# PowCarbinBoard_Isolation.net
KiCad netlist of a schematic drawn in Altium Designer
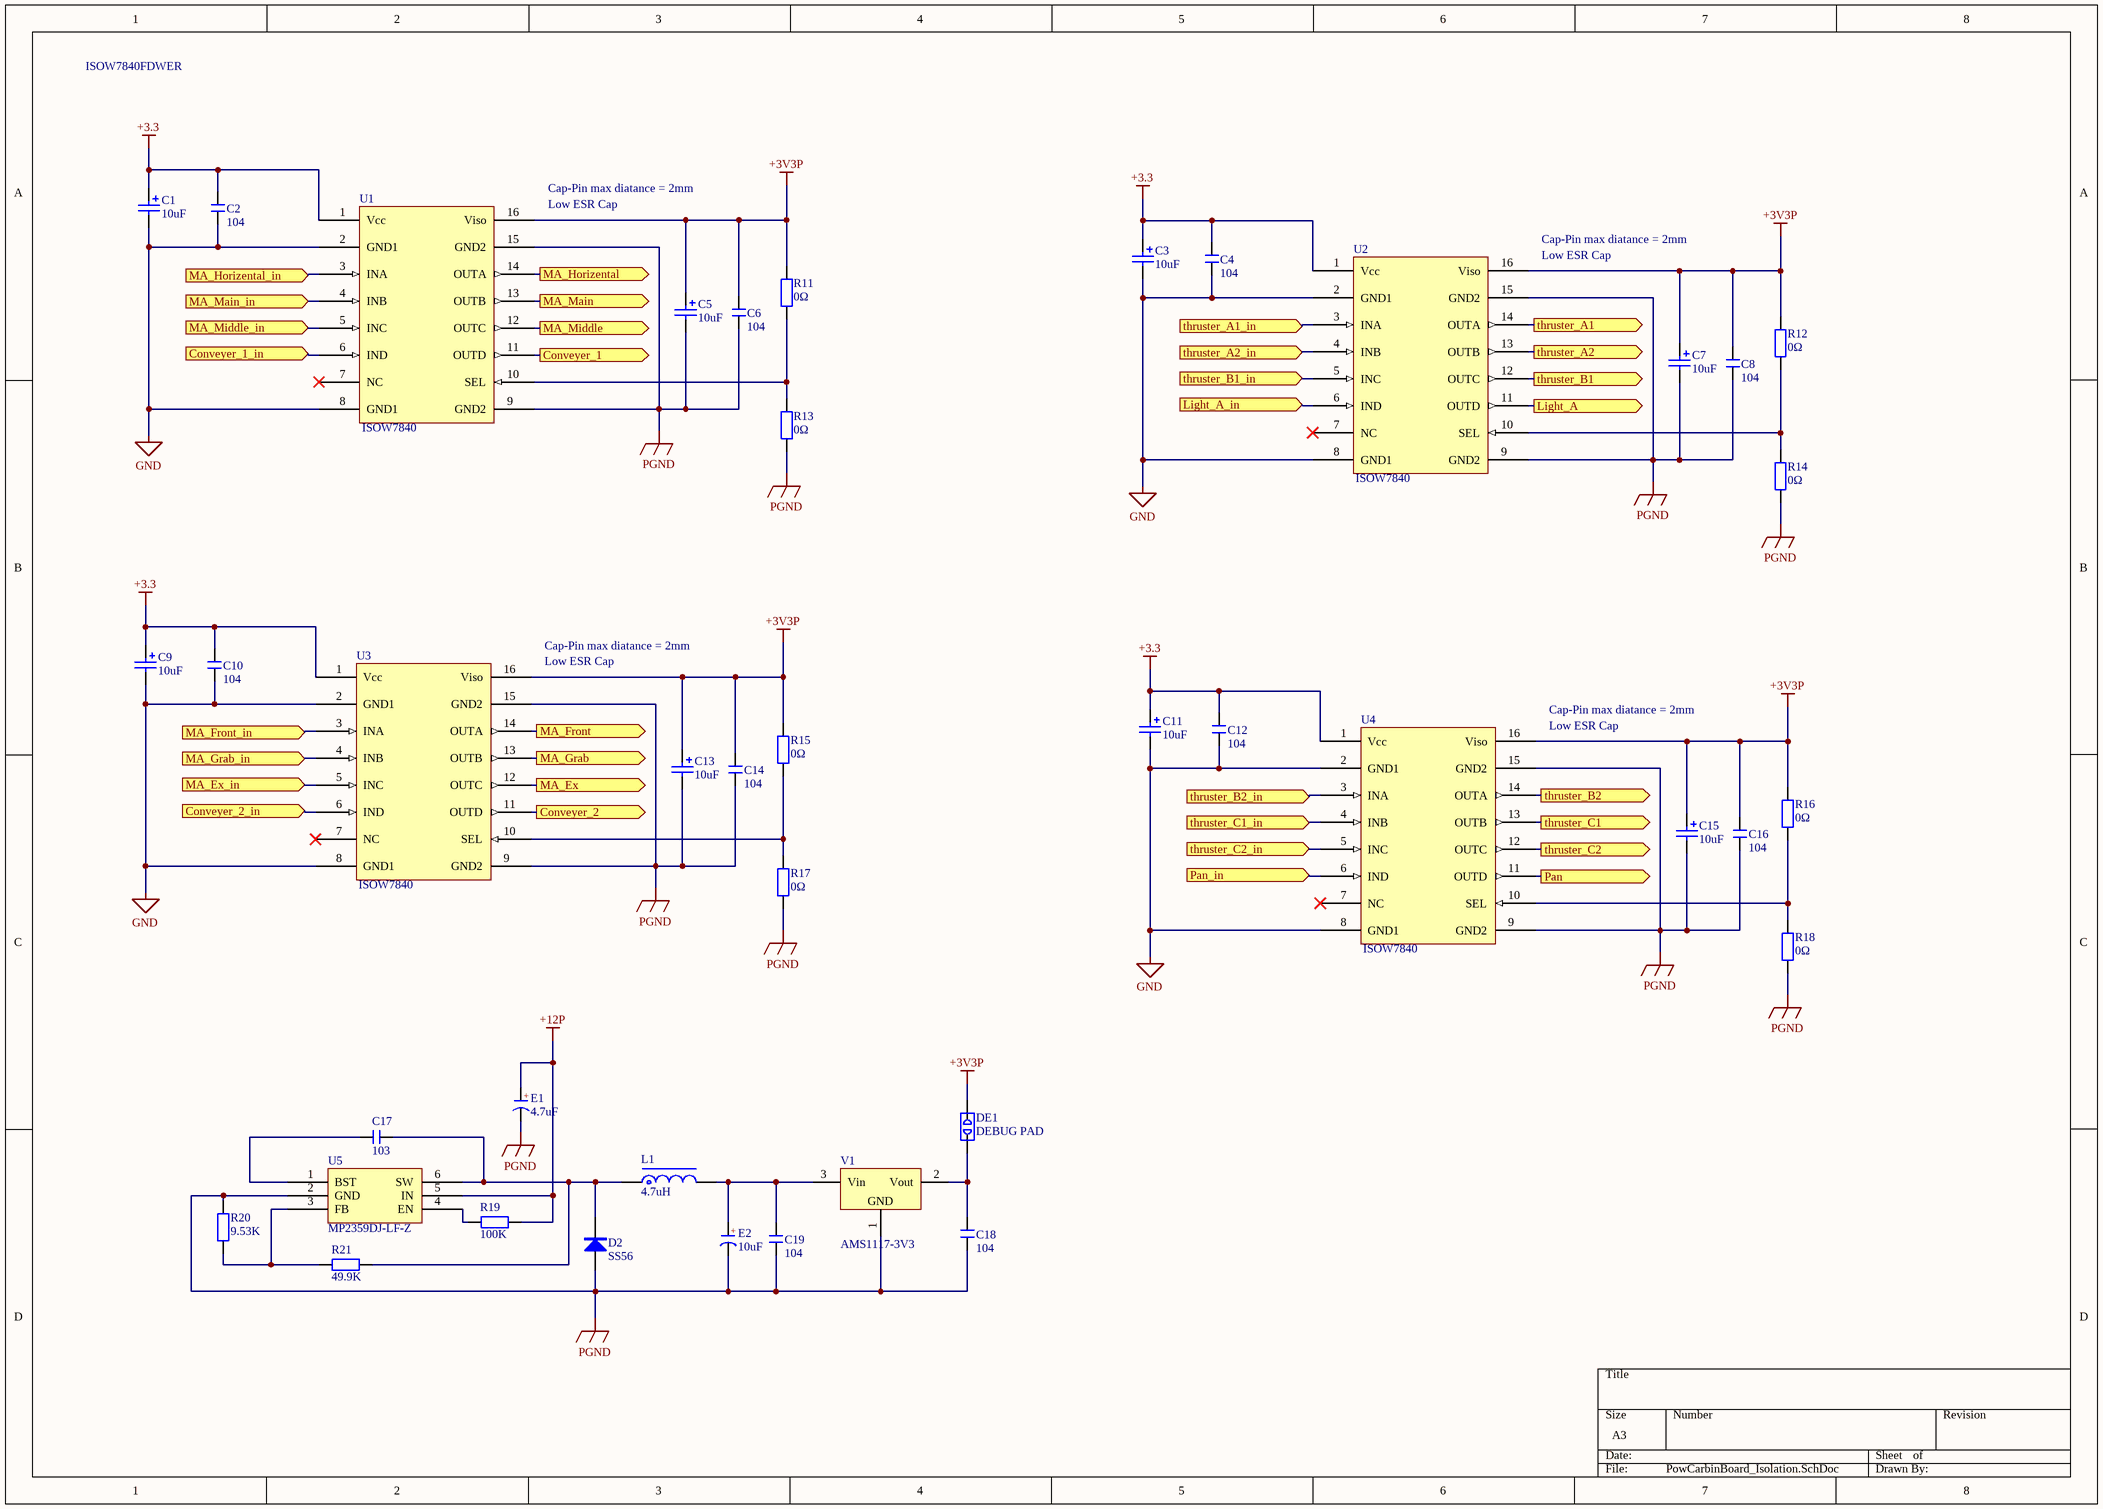
[diagram p0: PowCarbinBoard_Isolation.SchDoc]

(export (version "E")
  (design (tool "Eeschema 10.0.6"))
  (components
    (comp (ref "C1")
      (value "10uF")
      (footprint "CASE-B_3528")
      (description "钽电容")
      (libsource (lib "Miscellaneous Devices LC") (part "3528 100uF (107) 10% 6.3V"))
    )
    (comp (ref "C2")
      (value "104")
      (footprint "C 0603_L")
      (description "无极性贴片电容")
      (fields (field (name "版权归属") "源创客"))
      (libsource (lib "3.1   - 电阻-电容-电感") (part "C"))
    )
    (comp (ref "C3")
      (value "10uF")
      (footprint "CASE-B_3528")
      (description "钽电容")
      (libsource (lib "Miscellaneous Devices LC") (part "3528 100uF (107) 10% 6.3V"))
    )
    (comp (ref "C4")
      (value "104")
      (footprint "C 0603_L")
      (description "无极性贴片电容")
      (fields (field (name "版权归属") "源创客"))
      (libsource (lib "3.1   - 电阻-电容-电感") (part "C"))
    )
    (comp (ref "C5")
      (value "10uF")
      (footprint "CASE-B_3528")
      (description "钽电容")
      (libsource (lib "Miscellaneous Devices LC") (part "3528 100uF (107) 10% 6.3V"))
    )
    (comp (ref "C6")
      (value "104")
      (footprint "C 0603_L")
      (description "无极性贴片电容")
      (fields (field (name "版权归属") "源创客"))
      (libsource (lib "3.1   - 电阻-电容-电感") (part "C"))
    )
    (comp (ref "C7")
      (value "10uF")
      (footprint "CASE-B_3528")
      (description "钽电容")
      (libsource (lib "Miscellaneous Devices LC") (part "3528 100uF (107) 10% 6.3V"))
    )
    (comp (ref "C8")
      (value "104")
      (footprint "C 0603_L")
      (description "无极性贴片电容")
      (fields (field (name "版权归属") "源创客"))
      (libsource (lib "3.1   - 电阻-电容-电感") (part "C"))
    )
    (comp (ref "C9")
      (value "10uF")
      (footprint "CASE-B_3528")
      (description "钽电容")
      (libsource (lib "Miscellaneous Devices LC") (part "3528 100uF (107) 10% 6.3V"))
    )
    (comp (ref "C10")
      (value "104")
      (footprint "C 0603_L")
      (description "无极性贴片电容")
      (fields (field (name "版权归属") "源创客"))
      (libsource (lib "3.1   - 电阻-电容-电感") (part "C"))
    )
    (comp (ref "C11")
      (value "10uF")
      (footprint "CASE-B_3528")
      (description "钽电容")
      (libsource (lib "Miscellaneous Devices LC") (part "3528 100uF (107) 10% 6.3V"))
    )
    (comp (ref "C12")
      (value "104")
      (footprint "C 0603_L")
      (description "无极性贴片电容")
      (fields (field (name "版权归属") "源创客"))
      (libsource (lib "3.1   - 电阻-电容-电感") (part "C"))
    )
    (comp (ref "C13")
      (value "10uF")
      (footprint "CASE-B_3528")
      (description "钽电容")
      (libsource (lib "Miscellaneous Devices LC") (part "3528 100uF (107) 10% 6.3V"))
    )
    (comp (ref "C14")
      (value "104")
      (footprint "C 0603_L")
      (description "无极性贴片电容")
      (fields (field (name "版权归属") "源创客"))
      (libsource (lib "3.1   - 电阻-电容-电感") (part "C"))
    )
    (comp (ref "C15")
      (value "10uF")
      (footprint "CASE-B_3528")
      (description "钽电容")
      (libsource (lib "Miscellaneous Devices LC") (part "3528 100uF (107) 10% 6.3V"))
    )
    (comp (ref "C16")
      (value "104")
      (footprint "C 0603_L")
      (description "无极性贴片电容")
      (fields (field (name "版权归属") "源创客"))
      (libsource (lib "3.1   - 电阻-电容-电感") (part "C"))
    )
    (comp (ref "C17")
      (value "103")
      (footprint "C 0603_L")
      (description "无极性贴片电容")
      (fields (field (name "版权归属") "源创客"))
      (libsource (lib "3.1   - 电阻-电容-电感") (part "C"))
    )
    (comp (ref "C18")
      (value "104")
      (footprint "C 0603_L")
      (description "无极性贴片电容")
      (fields (field (name "版权归属") "源创客"))
      (libsource (lib "3.1   - 电阻-电容-电感") (part "C"))
    )
    (comp (ref "C19")
      (value "104")
      (footprint "C 0603_L")
      (description "无极性贴片电容")
      (fields (field (name "版权归属") "源创客"))
      (libsource (lib "3.1   - 电阻-电容-电感") (part "C"))
    )
    (comp (ref "D2")
      (value "SS56")
      (footprint "SMA")
      (description "肖特基二极管")
      (fields (field (name "版权归属") "源创客"))
      (libsource (lib "8.1   - 二极管-整流桥") (part "SS14"))
    )
    (comp (ref "DE1")
      (value "DEBUG PAD")
      (footprint "DEBUG_A")
      (description "调试断点焊盘")
      (fields (field (name "版权归属") "源创客"))
      (libsource (lib "15.1 - 未分类器件") (part "DEBUG"))
    )
    (comp (ref "E1")
      (value "4.7uF")
      (footprint "CM B(4*5.4)")
      (description "贴片电解电容")
      (fields (field (name "版权归属") "源创客"))
      (libsource (lib "3.1   - 电阻-电容-电感") (part "C-CM"))
    )
    (comp (ref "E2")
      (value "10uF")
      (footprint "CM B(4*5.4)")
      (description "贴片电解电容")
      (fields (field (name "版权归属") "源创客"))
      (libsource (lib "3.1   - 电阻-电容-电感") (part "C-CM"))
    )
    (comp (ref "L1")
      (value "4.7uH")
      (footprint "CDRH74")
      (description "功率屏蔽电感")
      (fields (field (name "版权归属") "源创客"))
      (libsource (lib "3.1   - 电阻-电容-电感") (part "L-CDRH"))
    )
    (comp (ref "R11")
      (value "0Ω")
      (footprint "R 0603_L")
      (description "贴片电阻")
      (fields (field (name "版权归属") "源创客"))
      (libsource (lib "3.1   - 电阻-电容-电感") (part "R"))
    )
    (comp (ref "R12")
      (value "0Ω")
      (footprint "R 0603_L")
      (description "贴片电阻")
      (fields (field (name "版权归属") "源创客"))
      (libsource (lib "3.1   - 电阻-电容-电感") (part "R"))
    )
    (comp (ref "R13")
      (value "0Ω")
      (footprint "R 0603_L")
      (description "贴片电阻")
      (fields (field (name "版权归属") "源创客"))
      (libsource (lib "3.1   - 电阻-电容-电感") (part "R"))
    )
    (comp (ref "R14")
      (value "0Ω")
      (footprint "R 0603_L")
      (description "贴片电阻")
      (fields (field (name "版权归属") "源创客"))
      (libsource (lib "3.1   - 电阻-电容-电感") (part "R"))
    )
    (comp (ref "R15")
      (value "0Ω")
      (footprint "R 0603_L")
      (description "贴片电阻")
      (fields (field (name "版权归属") "源创客"))
      (libsource (lib "3.1   - 电阻-电容-电感") (part "R"))
    )
    (comp (ref "R16")
      (value "0Ω")
      (footprint "R 0603_L")
      (description "贴片电阻")
      (fields (field (name "版权归属") "源创客"))
      (libsource (lib "3.1   - 电阻-电容-电感") (part "R"))
    )
    (comp (ref "R17")
      (value "0Ω")
      (footprint "R 0603_L")
      (description "贴片电阻")
      (fields (field (name "版权归属") "源创客"))
      (libsource (lib "3.1   - 电阻-电容-电感") (part "R"))
    )
    (comp (ref "R18")
      (value "0Ω")
      (footprint "R 0603_L")
      (description "贴片电阻")
      (fields (field (name "版权归属") "源创客"))
      (libsource (lib "3.1   - 电阻-电容-电感") (part "R"))
    )
    (comp (ref "R19")
      (value "100K")
      (footprint "R 0603_L")
      (description "贴片电阻")
      (fields (field (name "版权归属") "源创客"))
      (libsource (lib "3.1   - 电阻-电容-电感") (part "R"))
    )
    (comp (ref "R20")
      (value "9.53K")
      (footprint "R 0603_L")
      (description "贴片电阻")
      (fields (field (name "版权归属") "源创客"))
      (libsource (lib "3.1   - 电阻-电容-电感") (part "R"))
    )
    (comp (ref "R21")
      (value "49.9K")
      (footprint "R 0603_L")
      (description "贴片电阻")
      (fields (field (name "版权归属") "源创客"))
      (libsource (lib "3.1   - 电阻-电容-电感") (part "R"))
    )
    (comp (ref "U1") (value "ISOW7840") (footprint "ISOW7840") (libsource (lib "Schlib1") (part "ISOW7840")))
    (comp (ref "U2") (value "ISOW7840") (footprint "ISOW7840") (libsource (lib "Schlib1") (part "ISOW7840")))
    (comp (ref "U3") (value "ISOW7840") (footprint "ISOW7840") (libsource (lib "Schlib1") (part "ISOW7840")))
    (comp (ref "U4") (value "ISOW7840") (footprint "ISOW7840") (libsource (lib "Schlib1") (part "ISOW7840")))
    (comp (ref "U5")
      (value "MP2359DJ-LF-Z")
      (footprint "SOT-23-6")
      (description "DC-DC芯片")
      (libsource (lib "Miscellaneous Devices LC") (part "MP2359DJ-LF-Z_[C14259]"))
    )
    (comp (ref "V1")
      (value "AMS1117-3V3")
      (footprint "SOT89_N")
      (description "三端稳压芯片")
      (fields (field (name "版权归属") "源创客"))
      (libsource (lib "1.3   - 电源类芯片") (part "AMS1117"))
    )
  )
  (nets
    (net (code "1") (name "+3.3") (class "Default")
      (node (ref "C1") (pin "1") (pinfunction "1_1") (pintype "passive"))
      (node (ref "C10") (pin "2") (pinfunction "2_2") (pintype "passive"))
      (node (ref "C11") (pin "1") (pinfunction "1_1") (pintype "passive"))
      (node (ref "C12") (pin "2") (pinfunction "2_2") (pintype "passive"))
      (node (ref "C2") (pin "2") (pinfunction "2_2") (pintype "passive"))
      (node (ref "C3") (pin "1") (pinfunction "1_1") (pintype "passive"))
      (node (ref "C4") (pin "2") (pinfunction "2_2") (pintype "passive"))
      (node (ref "C9") (pin "1") (pinfunction "1_1") (pintype "passive"))
      (node (ref "U1") (pin "1") (pinfunction "Vcc_1") (pintype "power_in"))
      (node (ref "U2") (pin "1") (pinfunction "Vcc_1") (pintype "power_in"))
      (node (ref "U3") (pin "1") (pinfunction "Vcc_1") (pintype "power_in"))
      (node (ref "U4") (pin "1") (pinfunction "Vcc_1") (pintype "power_in"))
    )
    (net (code "2") (name "+3V3P") (class "Default")
      (node (ref "C13") (pin "1") (pinfunction "1_1") (pintype "passive"))
      (node (ref "C14") (pin "2") (pinfunction "2_2") (pintype "passive"))
      (node (ref "C15") (pin "1") (pinfunction "1_1") (pintype "passive"))
      (node (ref "C16") (pin "2") (pinfunction "2_2") (pintype "passive"))
      (node (ref "C5") (pin "1") (pinfunction "1_1") (pintype "passive"))
      (node (ref "C6") (pin "2") (pinfunction "2_2") (pintype "passive"))
      (node (ref "C7") (pin "1") (pinfunction "1_1") (pintype "passive"))
      (node (ref "C8") (pin "2") (pinfunction "2_2") (pintype "passive"))
      (node (ref "DE1") (pin "2") (pinfunction "2_2") (pintype "passive"))
      (node (ref "R11") (pin "2") (pinfunction "2_2") (pintype "passive"))
      (node (ref "R12") (pin "2") (pinfunction "2_2") (pintype "passive"))
      (node (ref "R15") (pin "2") (pinfunction "2_2") (pintype "passive"))
      (node (ref "R16") (pin "2") (pinfunction "2_2") (pintype "passive"))
      (node (ref "U1") (pin "16") (pinfunction "Viso_16") (pintype "power_in"))
      (node (ref "U2") (pin "16") (pinfunction "Viso_16") (pintype "power_in"))
      (node (ref "U3") (pin "16") (pinfunction "Viso_16") (pintype "power_in"))
      (node (ref "U4") (pin "16") (pinfunction "Viso_16") (pintype "power_in"))
    )
    (net (code "3") (name "+12P") (class "Default")
      (node (ref "E1") (pin "1") (pinfunction "A_1") (pintype "passive"))
      (node (ref "R19") (pin "1") (pinfunction "1_1") (pintype "passive"))
      (node (ref "U5") (pin "5") (pinfunction "IN_5") (pintype "passive"))
    )
    (net (code "4") (name "/Conveyer_1") (class "Default")
      (node (ref "U1") (pin "11") (pinfunction "OUTD_11") (pintype "output"))
    )
    (net (code "5") (name "/Conveyer_1_in") (class "Default")
      (node (ref "U1") (pin "6") (pinfunction "IND_6") (pintype "input"))
    )
    (net (code "6") (name "/Conveyer_2") (class "Default")
      (node (ref "U3") (pin "11") (pinfunction "OUTD_11") (pintype "output"))
    )
    (net (code "7") (name "/Conveyer_2_in") (class "Default")
      (node (ref "U3") (pin "6") (pinfunction "IND_6") (pintype "input"))
    )
    (net (code "8") (name "/Light_A") (class "Default")
      (node (ref "U2") (pin "11") (pinfunction "OUTD_11") (pintype "output"))
    )
    (net (code "9") (name "/Light_A_in") (class "Default")
      (node (ref "U2") (pin "6") (pinfunction "IND_6") (pintype "input"))
    )
    (net (code "10") (name "/MA_Ex") (class "Default")
      (node (ref "U3") (pin "12") (pinfunction "OUTC_12") (pintype "output"))
    )
    (net (code "11") (name "/MA_Ex_in") (class "Default")
      (node (ref "U3") (pin "5") (pinfunction "INC_5") (pintype "input"))
    )
    (net (code "12") (name "/MA_Front") (class "Default")
      (node (ref "U3") (pin "14") (pinfunction "OUTA_14") (pintype "output"))
    )
    (net (code "13") (name "/MA_Front_in") (class "Default")
      (node (ref "U3") (pin "3") (pinfunction "INA_3") (pintype "input"))
    )
    (net (code "14") (name "/MA_Grab") (class "Default")
      (node (ref "U3") (pin "13") (pinfunction "OUTB_13") (pintype "output"))
    )
    (net (code "15") (name "/MA_Grab_in") (class "Default")
      (node (ref "U3") (pin "4") (pinfunction "INB_4") (pintype "input"))
    )
    (net (code "16") (name "/MA_Horizental") (class "Default")
      (node (ref "U1") (pin "14") (pinfunction "OUTA_14") (pintype "output"))
    )
    (net (code "17") (name "/MA_Horizental_in") (class "Default")
      (node (ref "U1") (pin "3") (pinfunction "INA_3") (pintype "input"))
    )
    (net (code "18") (name "/MA_Main") (class "Default")
      (node (ref "U1") (pin "13") (pinfunction "OUTB_13") (pintype "output"))
    )
    (net (code "19") (name "/MA_Main_in") (class "Default")
      (node (ref "U1") (pin "4") (pinfunction "INB_4") (pintype "input"))
    )
    (net (code "20") (name "/MA_Middle") (class "Default")
      (node (ref "U1") (pin "12") (pinfunction "OUTC_12") (pintype "output"))
    )
    (net (code "21") (name "/MA_Middle_in") (class "Default")
      (node (ref "U1") (pin "5") (pinfunction "INC_5") (pintype "input"))
    )
    (net (code "22") (name "/Pan") (class "Default")
      (node (ref "U4") (pin "11") (pinfunction "OUTD_11") (pintype "output"))
    )
    (net (code "23") (name "/Pan_in") (class "Default")
      (node (ref "U4") (pin "6") (pinfunction "IND_6") (pintype "input"))
    )
    (net (code "24") (name "/thruster_A1") (class "Default")
      (node (ref "U2") (pin "14") (pinfunction "OUTA_14") (pintype "output"))
    )
    (net (code "25") (name "/thruster_A1_in") (class "Default")
      (node (ref "U2") (pin "3") (pinfunction "INA_3") (pintype "input"))
    )
    (net (code "26") (name "/thruster_A2") (class "Default")
      (node (ref "U2") (pin "13") (pinfunction "OUTB_13") (pintype "output"))
    )
    (net (code "27") (name "/thruster_A2_in") (class "Default")
      (node (ref "U2") (pin "4") (pinfunction "INB_4") (pintype "input"))
    )
    (net (code "28") (name "/thruster_B1") (class "Default")
      (node (ref "U2") (pin "12") (pinfunction "OUTC_12") (pintype "output"))
    )
    (net (code "29") (name "/thruster_B1_in") (class "Default")
      (node (ref "U2") (pin "5") (pinfunction "INC_5") (pintype "input"))
    )
    (net (code "30") (name "/thruster_B2") (class "Default")
      (node (ref "U4") (pin "14") (pinfunction "OUTA_14") (pintype "output"))
    )
    (net (code "31") (name "/thruster_B2_in") (class "Default")
      (node (ref "U4") (pin "3") (pinfunction "INA_3") (pintype "input"))
    )
    (net (code "32") (name "/thruster_C1") (class "Default")
      (node (ref "U4") (pin "13") (pinfunction "OUTB_13") (pintype "output"))
    )
    (net (code "33") (name "/thruster_C1_in") (class "Default")
      (node (ref "U4") (pin "4") (pinfunction "INB_4") (pintype "input"))
    )
    (net (code "34") (name "/thruster_C2") (class "Default")
      (node (ref "U4") (pin "12") (pinfunction "OUTC_12") (pintype "output"))
    )
    (net (code "35") (name "/thruster_C2_in") (class "Default")
      (node (ref "U4") (pin "5") (pinfunction "INC_5") (pintype "input"))
    )
    (net (code "36") (name "GND") (class "Default")
      (node (ref "C1") (pin "2") (pinfunction "2_2") (pintype "passive"))
      (node (ref "C10") (pin "1") (pinfunction "1_1") (pintype "passive"))
      (node (ref "C11") (pin "2") (pinfunction "2_2") (pintype "passive"))
      (node (ref "C12") (pin "1") (pinfunction "1_1") (pintype "passive"))
      (node (ref "C2") (pin "1") (pinfunction "1_1") (pintype "passive"))
      (node (ref "C3") (pin "2") (pinfunction "2_2") (pintype "passive"))
      (node (ref "C4") (pin "1") (pinfunction "1_1") (pintype "passive"))
      (node (ref "C9") (pin "2") (pinfunction "2_2") (pintype "passive"))
      (node (ref "U1") (pin "2") (pinfunction "GND1_2") (pintype "power_in"))
      (node (ref "U1") (pin "8") (pinfunction "GND1_8") (pintype "power_in"))
      (node (ref "U2") (pin "2") (pinfunction "GND1_2") (pintype "power_in"))
      (node (ref "U2") (pin "8") (pinfunction "GND1_8") (pintype "power_in"))
      (node (ref "U3") (pin "2") (pinfunction "GND1_2") (pintype "power_in"))
      (node (ref "U3") (pin "8") (pinfunction "GND1_8") (pintype "power_in"))
      (node (ref "U4") (pin "2") (pinfunction "GND1_2") (pintype "power_in"))
      (node (ref "U4") (pin "8") (pinfunction "GND1_8") (pintype "power_in"))
    )
    (net (code "37") (name "Net-(D2-K)") (class "Default")
      (node (ref "C17") (pin "1") (pinfunction "1_1") (pintype "passive"))
      (node (ref "D2") (pin "2") (pinfunction "K_2") (pintype "passive"))
      (node (ref "L1") (pin "1") (pinfunction "1_1") (pintype "passive"))
      (node (ref "R21") (pin "2") (pinfunction "2_2") (pintype "passive"))
      (node (ref "U5") (pin "6") (pinfunction "SW_6") (pintype "passive"))
    )
    (net (code "38") (name "Net-(E2-A)") (class "Default")
      (node (ref "C19") (pin "2") (pinfunction "2_2") (pintype "passive"))
      (node (ref "E2") (pin "1") (pinfunction "A_1") (pintype "passive"))
      (node (ref "L1") (pin "2") (pinfunction "2_2") (pintype "passive"))
      (node (ref "V1") (pin "3") (pinfunction "Vin_3") (pintype "passive"))
    )
    (net (code "39") (name "Net-(U1-SEL)") (class "Default")
      (node (ref "R11") (pin "1") (pinfunction "1_1") (pintype "passive"))
      (node (ref "R13") (pin "2") (pinfunction "2_2") (pintype "passive"))
      (node (ref "U1") (pin "10") (pinfunction "SEL_10") (pintype "input"))
    )
    (net (code "40") (name "Net-(U2-SEL)") (class "Default")
      (node (ref "R12") (pin "1") (pinfunction "1_1") (pintype "passive"))
      (node (ref "R14") (pin "2") (pinfunction "2_2") (pintype "passive"))
      (node (ref "U2") (pin "10") (pinfunction "SEL_10") (pintype "input"))
    )
    (net (code "41") (name "Net-(U3-SEL)") (class "Default")
      (node (ref "R15") (pin "1") (pinfunction "1_1") (pintype "passive"))
      (node (ref "R17") (pin "2") (pinfunction "2_2") (pintype "passive"))
      (node (ref "U3") (pin "10") (pinfunction "SEL_10") (pintype "input"))
    )
    (net (code "42") (name "Net-(U4-SEL)") (class "Default")
      (node (ref "R16") (pin "1") (pinfunction "1_1") (pintype "passive"))
      (node (ref "R18") (pin "2") (pinfunction "2_2") (pintype "passive"))
      (node (ref "U4") (pin "10") (pinfunction "SEL_10") (pintype "input"))
    )
    (net (code "43") (name "Net-(U5-BST)") (class "Default")
      (node (ref "C17") (pin "2") (pinfunction "2_2") (pintype "passive"))
      (node (ref "U5") (pin "1") (pinfunction "BST_1") (pintype "passive"))
    )
    (net (code "44") (name "Net-(U5-EN)") (class "Default")
      (node (ref "R19") (pin "2") (pinfunction "2_2") (pintype "passive"))
      (node (ref "U5") (pin "4") (pinfunction "EN_4") (pintype "passive"))
    )
    (net (code "45") (name "Net-(U5-FB)") (class "Default")
      (node (ref "R20") (pin "1") (pinfunction "1_1") (pintype "passive"))
      (node (ref "R21") (pin "1") (pinfunction "1_1") (pintype "passive"))
      (node (ref "U5") (pin "3") (pinfunction "FB_3") (pintype "passive"))
    )
    (net (code "46") (name "Net-(V1-Vout)") (class "Default")
      (node (ref "C18") (pin "2") (pinfunction "2_2") (pintype "passive"))
      (node (ref "DE1") (pin "1") (pinfunction "1_1") (pintype "passive"))
      (node (ref "V1") (pin "2") (pinfunction "Vout_2") (pintype "passive"))
    )
    (net (code "47") (name "PGND") (class "Default")
      (node (ref "C13") (pin "2") (pinfunction "2_2") (pintype "passive"))
      (node (ref "C14") (pin "1") (pinfunction "1_1") (pintype "passive"))
      (node (ref "C15") (pin "2") (pinfunction "2_2") (pintype "passive"))
      (node (ref "C16") (pin "1") (pinfunction "1_1") (pintype "passive"))
      (node (ref "C18") (pin "1") (pinfunction "1_1") (pintype "passive"))
      (node (ref "C19") (pin "1") (pinfunction "1_1") (pintype "passive"))
      (node (ref "C5") (pin "2") (pinfunction "2_2") (pintype "passive"))
      (node (ref "C6") (pin "1") (pinfunction "1_1") (pintype "passive"))
      (node (ref "C7") (pin "2") (pinfunction "2_2") (pintype "passive"))
      (node (ref "C8") (pin "1") (pinfunction "1_1") (pintype "passive"))
      (node (ref "D2") (pin "1") (pinfunction "A_1") (pintype "passive"))
      (node (ref "E1") (pin "2") (pinfunction "K_2") (pintype "passive"))
      (node (ref "E2") (pin "2") (pinfunction "K_2") (pintype "passive"))
      (node (ref "R13") (pin "1") (pinfunction "1_1") (pintype "passive"))
      (node (ref "R14") (pin "1") (pinfunction "1_1") (pintype "passive"))
      (node (ref "R17") (pin "1") (pinfunction "1_1") (pintype "passive"))
      (node (ref "R18") (pin "1") (pinfunction "1_1") (pintype "passive"))
      (node (ref "R20") (pin "2") (pinfunction "2_2") (pintype "passive"))
      (node (ref "U1") (pin "15") (pinfunction "GND2_15") (pintype "power_in"))
      (node (ref "U1") (pin "9") (pinfunction "GND2_9") (pintype "power_in"))
      (node (ref "U2") (pin "15") (pinfunction "GND2_15") (pintype "power_in"))
      (node (ref "U2") (pin "9") (pinfunction "GND2_9") (pintype "power_in"))
      (node (ref "U3") (pin "15") (pinfunction "GND2_15") (pintype "power_in"))
      (node (ref "U3") (pin "9") (pinfunction "GND2_9") (pintype "power_in"))
      (node (ref "U4") (pin "15") (pinfunction "GND2_15") (pintype "power_in"))
      (node (ref "U4") (pin "9") (pinfunction "GND2_9") (pintype "power_in"))
      (node (ref "U5") (pin "2") (pinfunction "GND_2") (pintype "passive"))
      (node (ref "V1") (pin "1") (pinfunction "GND_1") (pintype "passive"))
    )
    (net (code "48") (name "unconnected-(U1-NC-Pad7)") (class "Default")
      (node (ref "U1") (pin "7") (pinfunction "NC_7") (pintype "passive+no_connect"))
    )
    (net (code "49") (name "unconnected-(U2-NC-Pad7)") (class "Default")
      (node (ref "U2") (pin "7") (pinfunction "NC_7") (pintype "passive+no_connect"))
    )
    (net (code "50") (name "unconnected-(U3-NC-Pad7)") (class "Default")
      (node (ref "U3") (pin "7") (pinfunction "NC_7") (pintype "passive+no_connect"))
    )
    (net (code "51") (name "unconnected-(U4-NC-Pad7)") (class "Default")
      (node (ref "U4") (pin "7") (pinfunction "NC_7") (pintype "passive+no_connect"))
    )
  )
)
